# half_bridge.net
KiCad netlist of a schematic drawn in Altium Designer
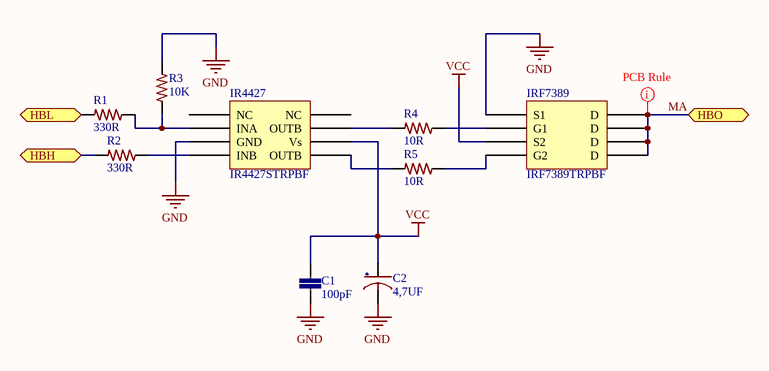
[diagram p0: half_bridge.SchDoc]

(export (version "E")
  (design (tool "Eeschema 10.0.6"))
  (components
    (comp (ref "C1")
      (value "100pF")
      (footprint "0402-CAP")
      (description "CAP CER 100PF 50V 1% NP0 0402")
      (fields (field (name "PART NO") "GRM1555C1H101FA01D"))
      (libsource (lib "IMBEL") (part "CAPACITOR"))
    )
    (comp (ref "C2")
      (value "4,7UF")
      (footprint "PCBComponent")
      (description "Tantalum Capacitors - Solid SMD 10uF 35V 10% L ESR")
      (libsource (lib "IMBEL") (part "TPSD106K035R0300-01.A.1"))
    )
    (comp (ref "IR4427")
      (value "IR4427STRPBF")
      (footprint "IR4427-PCB")
      (description "IC DRIVER DUAL LOW SIDE 8-DIP")
      (libsource (lib "Schlib1") (part "IR4427"))
    )
    (comp (ref "IRF7389")
      (value "IRF7389TRPBF")
      (footprint "IRF7389-PCB")
      (description "MOSFET N/P-CH 30V 8-SOIC")
      (libsource (lib "Schlib1") (part "IRF7389"))
    )
    (comp (ref "R1")
      (value "330R")
      (footprint "0402-RES-HD")
      (description "RES 330 OHM 1/10W 1% 0402 SMD")
      (fields (field (name "PART NO") "ERJ-2RKF3300X"))
      (libsource (lib "IMBEL") (part "RESISTOR"))
    )
    (comp (ref "R2")
      (value "330R")
      (footprint "0402-RES-HD")
      (description "RES 330 OHM 1/10W 1% 0402 SMD")
      (fields (field (name "PART NO") "ERJ-2RKF3300X"))
      (libsource (lib "IMBEL") (part "R0402-330R-7"))
    )
    (comp (ref "R3")
      (value "10K")
      (footprint "0402-RES-HD")
      (description "RES 10K OHM 1/10W 1% 0402 SMD")
      (fields (field (name "PART NO") "ERJ-2RKF1002X"))
      (libsource (lib "IMBEL") (part "R0402-10K-10"))
    )
    (comp (ref "R4")
      (value "10R")
      (footprint "0402-RES-HD")
      (description "RES 10 OHM 1/10W 1% 0402 SMD")
      (fields (field (name "PART NO") "ERJ-2RKF10R0X"))
      (libsource (lib "IMBEL") (part "RESISTOR"))
    )
    (comp (ref "R5")
      (value "10R")
      (footprint "0402-RES-HD")
      (description "RES 10 OHM 1/10W 1% 0402 SMD")
      (fields (field (name "PART NO") "ERJ-2RKF10R0X"))
      (libsource (lib "IMBEL") (part "R0402-10R-6"))
    )
  )
  (nets
    (net (code "1") (name "/HBH") (class "Default")
      (node (ref "R2") (pin "1") (pinfunction "1_1") (pintype "passive"))
    )
    (net (code "2") (name "/HBL") (class "Default")
      (node (ref "R1") (pin "1") (pinfunction "1_1") (pintype "passive"))
    )
    (net (code "3") (name "/MA") (class "Default")
      (node (ref "IRF7389") (pin "5") (pinfunction "D_5") (pintype "passive"))
      (node (ref "IRF7389") (pin "6") (pinfunction "D_6") (pintype "passive"))
      (node (ref "IRF7389") (pin "7") (pinfunction "D_7") (pintype "passive"))
      (node (ref "IRF7389") (pin "8") (pinfunction "D_8") (pintype "passive"))
    )
    (net (code "4") (name "GND") (class "Default")
      (node (ref "C1") (pin "2") (pinfunction "2_2") (pintype "passive"))
      (node (ref "C2") (pin "2") (pinfunction "-_2") (pintype "passive"))
      (node (ref "IR4427") (pin "3") (pinfunction "GND_3") (pintype "passive"))
      (node (ref "IRF7389") (pin "1") (pinfunction "S1_1") (pintype "passive"))
      (node (ref "R3") (pin "1") (pinfunction "1_1") (pintype "passive"))
    )
    (net (code "5") (name "Net-(IR4427-INA)") (class "Default")
      (node (ref "IR4427") (pin "2") (pinfunction "INA_2") (pintype "passive"))
      (node (ref "R1") (pin "2") (pinfunction "2_2") (pintype "passive"))
      (node (ref "R3") (pin "2") (pinfunction "2_2") (pintype "passive"))
    )
    (net (code "6") (name "Net-(IR4427-INB)") (class "Default")
      (node (ref "IR4427") (pin "4") (pinfunction "INB_4") (pintype "passive"))
      (node (ref "R2") (pin "2") (pinfunction "2_2") (pintype "passive"))
    )
    (net (code "7") (name "Net-(IR4427-OUTB-Pad5)") (class "Default")
      (node (ref "IR4427") (pin "5") (pinfunction "OUTB_5") (pintype "passive"))
      (node (ref "R5") (pin "1") (pinfunction "1_1") (pintype "passive"))
    )
    (net (code "8") (name "Net-(IR4427-OUTB-Pad7)") (class "Default")
      (node (ref "IR4427") (pin "7") (pinfunction "OUTB_7") (pintype "passive"))
      (node (ref "R4") (pin "1") (pinfunction "1_1") (pintype "passive"))
    )
    (net (code "9") (name "Net-(IRF7389-G1)") (class "Default")
      (node (ref "IRF7389") (pin "2") (pinfunction "G1_2") (pintype "passive"))
      (node (ref "R4") (pin "2") (pinfunction "2_2") (pintype "passive"))
    )
    (net (code "10") (name "Net-(IRF7389-G2)") (class "Default")
      (node (ref "IRF7389") (pin "4") (pinfunction "G2_4") (pintype "passive"))
      (node (ref "R5") (pin "2") (pinfunction "2_2") (pintype "passive"))
    )
    (net (code "11") (name "VCC") (class "Default")
      (node (ref "C1") (pin "1") (pinfunction "1_1") (pintype "passive"))
      (node (ref "C2") (pin "1") (pinfunction "+_1") (pintype "passive"))
      (node (ref "IR4427") (pin "6") (pinfunction "Vs_6") (pintype "passive"))
      (node (ref "IRF7389") (pin "3") (pinfunction "S2_3") (pintype "passive"))
    )
    (net (code "12") (name "unconnected-(IR4427-NC-Pad1)") (class "Default")
      (node (ref "IR4427") (pin "1") (pinfunction "NC_1") (pintype "passive"))
    )
    (net (code "13") (name "unconnected-(IR4427-NC-Pad8)") (class "Default")
      (node (ref "IR4427") (pin "8") (pinfunction "NC_8") (pintype "passive"))
    )
  )
)
